# 04-AT86RF215IQ.net
KiCad netlist of a schematic drawn in Altium Designer
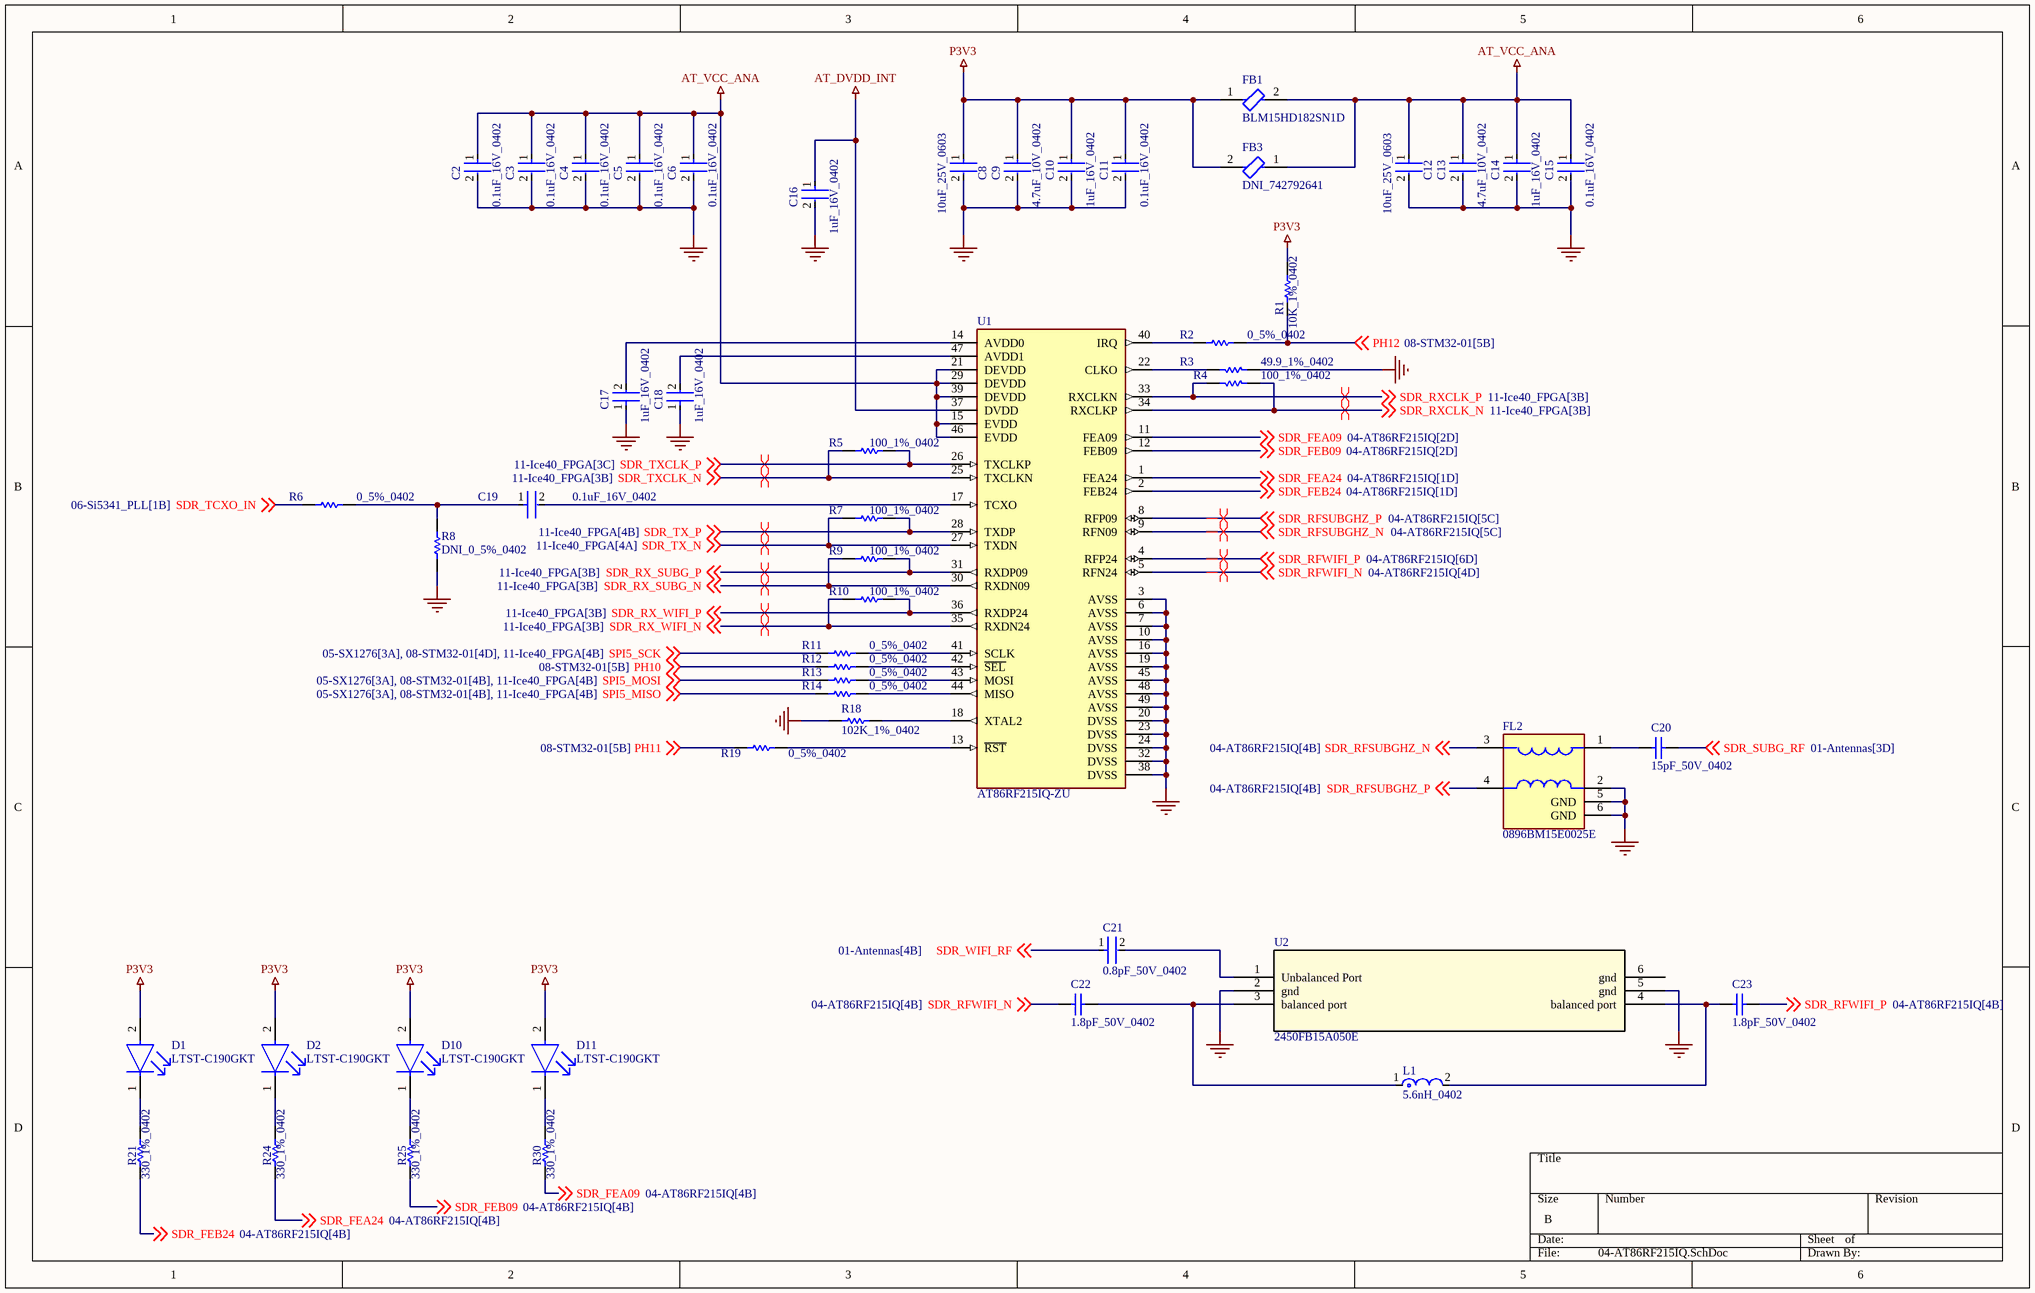
[diagram p0: 04-AT86RF215IQ.SchDoc]

(export (version "E")
  (design (tool "Eeschema 10.0.6"))
  (components
    (comp (ref "C2")
      (value "0.1uF_16V_0402")
      (footprint "FP-C0402-BB-MFG")
      (description "CAP CER 0.1UF 16V 5% X7R 0402")
      (fields
        (field (name "MANUFACTURER") "Kemet")
        (field (name "MANUFACTURER PART NUMBER") "C0402C104J4RACTU")
      )
      (libsource (lib "Altium Content Vault") (part "b4654b650e69147ec39a6b967a45e02"))
    )
    (comp (ref "C3")
      (value "0.1uF_16V_0402")
      (footprint "FP-C0402-BB-MFG")
      (description "CAP CER 0.1UF 16V 5% X7R 0402")
      (fields
        (field (name "MANUFACTURER") "Kemet")
        (field (name "MANUFACTURER PART NUMBER") "C0402C104J4RACTU")
      )
      (libsource (lib "Altium Content Vault") (part "b4654b650e69147ec39a6b967a45e02"))
    )
    (comp (ref "C4")
      (value "0.1uF_16V_0402")
      (footprint "FP-C0402-BB-MFG")
      (description "CAP CER 0.1UF 16V 5% X7R 0402")
      (fields
        (field (name "MANUFACTURER") "Kemet")
        (field (name "MANUFACTURER PART NUMBER") "C0402C104J4RACTU")
      )
      (libsource (lib "Altium Content Vault") (part "b4654b650e69147ec39a6b967a45e02"))
    )
    (comp (ref "C5")
      (value "0.1uF_16V_0402")
      (footprint "FP-C0402-BB-MFG")
      (description "CAP CER 0.1UF 16V 5% X7R 0402")
      (fields
        (field (name "MANUFACTURER") "Kemet")
        (field (name "MANUFACTURER PART NUMBER") "C0402C104J4RACTU")
      )
      (libsource (lib "Altium Content Vault") (part "b4654b650e69147ec39a6b967a45e02"))
    )
    (comp (ref "C6")
      (value "0.1uF_16V_0402")
      (footprint "FP-C0402-BB-MFG")
      (description "CAP CER 0.1UF 16V 5% X7R 0402")
      (fields
        (field (name "MANUFACTURER") "Kemet")
        (field (name "MANUFACTURER PART NUMBER") "C0402C104J4RACTU")
      )
      (libsource (lib "Altium Content Vault") (part "b4654b650e69147ec39a6b967a45e02"))
    )
    (comp (ref "C8")
      (value "10uF_25V_0603")
      (footprint "FP-CL10-IPC_C")
      (description "Cap Ceramic 10uF 25V X5R ±20% Pad SMD 0603 +85°C T/R")
      (fields (field (name "TOLERANCE") "20%"))
      (libsource (lib "Altium Content Vault") (part "b4654b650e69147ec39a6b967a45e02"))
    )
    (comp (ref "C9")
      (value "4.7uF_10V_0402")
      (footprint "FP-C1005-050-0_15-MFG")
      (description "CAP CER 4.7UF 10V X5R 0402")
      (fields (field (name "TOLERANCE") "10%"))
      (libsource (lib "Altium Content Vault") (part "b4654b650e69147ec39a6b967a45e02"))
    )
    (comp (ref "C10")
      (value "1uF_16V_0402")
      (footprint "FP-0402-L_1_0_0_05-W_0_5-IPC_A")
      (description "None")
      (fields (field (name "TOLERANCE") "10%"))
      (libsource (lib "Altium Content Vault") (part "b4654b650e69147ec39a6b967a45e02"))
    )
    (comp (ref "C11")
      (value "0.1uF_16V_0402")
      (footprint "FP-C0402-BB-MFG")
      (description "CAP CER 0.1UF 16V 5% X7R 0402")
      (fields
        (field (name "MANUFACTURER") "Kemet")
        (field (name "MANUFACTURER PART NUMBER") "C0402C104J4RACTU")
      )
      (libsource (lib "Altium Content Vault") (part "b4654b650e69147ec39a6b967a45e02"))
    )
    (comp (ref "C12")
      (value "10uF_25V_0603")
      (footprint "FP-CL10-IPC_C")
      (description "Cap Ceramic 10uF 25V X5R ±20% Pad SMD 0603 +85°C T/R")
      (fields (field (name "TOLERANCE") "20%"))
      (libsource (lib "Altium Content Vault") (part "b4654b650e69147ec39a6b967a45e02"))
    )
    (comp (ref "C13")
      (value "4.7uF_10V_0402")
      (footprint "FP-C1005-050-0_15-MFG")
      (description "CAP CER 4.7UF 10V X5R 0402")
      (fields (field (name "TOLERANCE") "10%"))
      (libsource (lib "Altium Content Vault") (part "b4654b650e69147ec39a6b967a45e02"))
    )
    (comp (ref "C14")
      (value "1uF_16V_0402")
      (footprint "FP-0402-L_1_0_0_05-W_0_5-IPC_A")
      (description "None")
      (fields (field (name "TOLERANCE") "10%"))
      (libsource (lib "Altium Content Vault") (part "b4654b650e69147ec39a6b967a45e02"))
    )
    (comp (ref "C15")
      (value "0.1uF_16V_0402")
      (footprint "FP-C0402-BB-MFG")
      (description "CAP CER 0.1UF 16V 5% X7R 0402")
      (fields
        (field (name "MANUFACTURER") "Kemet")
        (field (name "MANUFACTURER PART NUMBER") "C0402C104J4RACTU")
      )
      (libsource (lib "Altium Content Vault") (part "b4654b650e69147ec39a6b967a45e02"))
    )
    (comp (ref "C16")
      (value "1uF_16V_0402")
      (footprint "FP-0402-L_1_0_0_05-W_0_5-IPC_A")
      (description "None")
      (fields (field (name "TOLERANCE") "10%"))
      (libsource (lib "Altium Content Vault") (part "b4654b650e69147ec39a6b967a45e02"))
    )
    (comp (ref "C17")
      (value "1uF_16V_0402")
      (footprint "FP-0402-L_1_0_0_05-W_0_5-IPC_A")
      (description "None")
      (fields (field (name "TOLERANCE") "10%"))
      (libsource (lib "Altium Content Vault") (part "b4654b650e69147ec39a6b967a45e02"))
    )
    (comp (ref "C18")
      (value "1uF_16V_0402")
      (footprint "FP-0402-L_1_0_0_05-W_0_5-IPC_A")
      (description "None")
      (fields (field (name "TOLERANCE") "10%"))
      (libsource (lib "Altium Content Vault") (part "b4654b650e69147ec39a6b967a45e02"))
    )
    (comp (ref "C19")
      (value "0.1uF_16V_0402")
      (footprint "FP-C0402-BB-MFG")
      (description "CAP CER 0.1UF 16V 5% X7R 0402")
      (fields
        (field (name "MANUFACTURER") "Kemet")
        (field (name "MANUFACTURER PART NUMBER") "C0402C104J4RACTU")
      )
      (libsource (lib "Altium Content Vault") (part "b4654b650e69147ec39a6b967a45e02"))
    )
    (comp (ref "C20")
      (value "15pF_50V_0402")
      (footprint "CAPC1608X90X35ML10T15")
      (fields (field (name "PART NUMBER") "GRM1885C1H150JA01D") (field (name "MANUFACTURER") "Murata"))
      (libsource (lib "Altium Content Vault") (part "CAP"))
    )
    (comp (ref "C21")
      (value "0.8pF_50V_0402")
      (footprint "FP-GJM155-0_05-IPC_A")
      (description "Multi-Layer Ceramic Capacitor 0.8pF C0G  ±0.1pF 0402 Paper T/R")
      (fields (field (name "VOLTAGE") "50V"))
      (libsource (lib "Altium Content Vault") (part "02cd4be3c70576c341d710602a673aa"))
    )
    (comp (ref "C22")
      (value "1.8pF_50V_0402")
      (footprint "CAPC1005X55X25LL05T10")
      (fields (field (name "PART NUMBER") "GRM1555C1H1R8CA01D") (field (name "MANUFACTURER") "Murata"))
      (libsource (lib "Altium Content Vault") (part "CAP"))
    )
    (comp (ref "C23")
      (value "1.8pF_50V_0402")
      (footprint "CAPC1005X55X25LL05T10")
      (fields (field (name "PART NUMBER") "GRM1555C1H1R8CA01D") (field (name "MANUFACTURER") "Murata"))
      (libsource (lib "Altium Content Vault") (part "CAP"))
    )
    (comp (ref "D1")
      (value "LTST-C190GKT")
      (footprint "FP-LTST-C190GKT-MFG")
      (description "LED GREEN CLEAR CHIP SMD")
      (fields (field (name "VOLTAGE") "2V"))
      (libsource (lib "Altium Content Vault") (part "8706943c75ba83719d021d2fdc84c58"))
    )
    (comp (ref "D2")
      (value "LTST-C190GKT")
      (footprint "FP-LTST-C190GKT-MFG")
      (description "LED GREEN CLEAR CHIP SMD")
      (fields (field (name "VOLTAGE") "2V"))
      (libsource (lib "Altium Content Vault") (part "8706943c75ba83719d021d2fdc84c58"))
    )
    (comp (ref "D10")
      (value "LTST-C190GKT")
      (footprint "FP-LTST-C190GKT-MFG")
      (description "LED GREEN CLEAR CHIP SMD")
      (fields (field (name "VOLTAGE") "2V"))
      (libsource (lib "Altium Content Vault") (part "8706943c75ba83719d021d2fdc84c58"))
    )
    (comp (ref "D11")
      (value "LTST-C190GKT")
      (footprint "FP-LTST-C190GKT-MFG")
      (description "LED GREEN CLEAR CHIP SMD")
      (fields (field (name "VOLTAGE") "2V"))
      (libsource (lib "Altium Content Vault") (part "8706943c75ba83719d021d2fdc84c58"))
    )
    (comp (ref "FB1")
      (value "BLM15HD182SN1D")
      (footprint "FP-BLM15-0_05-MFG")
      (description "Chip Ferrite Bead, 0402, 1800Ω @ 100MHz, 2.2Ω, 25%, 200mA")
      (fields (field (name "TOLERANCE") "25%"))
      (libsource (lib "Altium Content Vault") (part "5f30dd21d616792df468990f7003faa"))
    )
    (comp (ref "FB3")
      (value "DNI_742792641")
      (footprint "FP-742792641-MFG")
      (description "FERRITE BEAD 300 OHM 0603 1LN")
      (fields (field (name "TOLERANCE") "25%"))
      (libsource (lib "Altium Content Vault") (part "5f30dd21d616792df468990f7003faa"))
    )
    (comp (ref "FL2")
      (value "0896BM15E0025E")
      (footprint "FP-0896BM15E0025E-MFG")
      (description "BALUN 863MHZ-928MHZ 50/50 0805")
      (fields
        (field (name "MANUFACTURER") "Johanson")
        (field (name "OCTOPART") "https://octopart.com/0896bm15e0025e-johanson-71691697")
      )
      (libsource (lib "Altium Content Vault") (part "9725e6fc3b6d4b71249fb6cd7b91a1d"))
    )
    (comp (ref "L1")
      (value "5.6nH_0402")
      (footprint "FP-LQG15HH_02-IPC_A")
      (description "Multilayer type RF Inductor 5.6nH ±0.3nH 0.18Ω 600mA 0402")
      (libsource (lib "Altium Content Vault") (part "4cc4b267dca4c8e51f7102f422741d8"))
    )
    (comp (ref "R1")
      (value "10K_1%_0402")
      (footprint "RESC1005X40X25NL10T10")
      (fields (field (name "MANUFACTURER") "Bourns") (field (name "PART NUMBER") "CR0402-FX-1002GLF"))
      (libsource (lib "Altium Content Vault") (part "RES"))
    )
    (comp (ref "R2")
      (value "0_5%_0402")
      (footprint "RESC1005X40X25NL05T10")
      (fields (field (name "MANUFACTURER") "Panasonic") (field (name "PART NUMBER") "ERJ-U020R00X"))
      (libsource (lib "Altium Content Vault") (part "RES"))
    )
    (comp (ref "R3")
      (value "49.9_1%_0402")
      (footprint "RESC1005X40X25NL10T10")
      (fields (field (name "PART NUMBER") "RK73H1ETTP49R9F") (field (name "MANUFACTURER") "KOA Speer"))
      (libsource (lib "Altium Content Vault") (part "RES"))
    )
    (comp (ref "R4")
      (value "100_1%_0402")
      (footprint "RESC1005X40X25NL05T10")
      (fields (field (name "MANUFACTURER") "Yageo") (field (name "PART NUMBER") "RC0402FR-13100RL"))
      (libsource (lib "Altium Content Vault") (part "RES"))
    )
    (comp (ref "R5")
      (value "100_1%_0402")
      (footprint "RESC1005X40X25NL05T10")
      (fields (field (name "MANUFACTURER") "Yageo") (field (name "PART NUMBER") "RC0402FR-13100RL"))
      (libsource (lib "Altium Content Vault") (part "RES"))
    )
    (comp (ref "R6")
      (value "0_5%_0402")
      (footprint "RESC1005X40X25NL05T10")
      (fields (field (name "MANUFACTURER") "Panasonic") (field (name "PART NUMBER") "ERJ-U020R00X"))
      (libsource (lib "Altium Content Vault") (part "RES"))
    )
    (comp (ref "R7")
      (value "100_1%_0402")
      (footprint "RESC1005X40X25NL05T10")
      (fields (field (name "MANUFACTURER") "Yageo") (field (name "PART NUMBER") "RC0402FR-13100RL"))
      (libsource (lib "Altium Content Vault") (part "RES"))
    )
    (comp (ref "R8")
      (value "DNI_0_5%_0402")
      (footprint "RESC1005X40X25NL05T10")
      (fields (field (name "MANUFACTURER") "Panasonic") (field (name "PART NUMBER") "ERJ-U020R00X"))
      (libsource (lib "Altium Content Vault") (part "RES"))
    )
    (comp (ref "R9")
      (value "100_1%_0402")
      (footprint "RESC1005X40X25NL05T10")
      (fields (field (name "MANUFACTURER") "Yageo") (field (name "PART NUMBER") "RC0402FR-13100RL"))
      (libsource (lib "Altium Content Vault") (part "RES"))
    )
    (comp (ref "R10")
      (value "100_1%_0402")
      (footprint "RESC1005X40X25NL05T10")
      (fields (field (name "MANUFACTURER") "Yageo") (field (name "PART NUMBER") "RC0402FR-13100RL"))
      (libsource (lib "Altium Content Vault") (part "RES"))
    )
    (comp (ref "R11")
      (value "0_5%_0402")
      (footprint "RESC1005X40X25NL05T10")
      (fields (field (name "MANUFACTURER") "Panasonic") (field (name "PART NUMBER") "ERJ-U020R00X"))
      (libsource (lib "Altium Content Vault") (part "RES"))
    )
    (comp (ref "R12")
      (value "0_5%_0402")
      (footprint "RESC1005X40X25NL05T10")
      (fields (field (name "MANUFACTURER") "Panasonic") (field (name "PART NUMBER") "ERJ-U020R00X"))
      (libsource (lib "Altium Content Vault") (part "RES"))
    )
    (comp (ref "R13")
      (value "0_5%_0402")
      (footprint "RESC1005X40X25NL05T10")
      (fields (field (name "MANUFACTURER") "Panasonic") (field (name "PART NUMBER") "ERJ-U020R00X"))
      (libsource (lib "Altium Content Vault") (part "RES"))
    )
    (comp (ref "R14")
      (value "0_5%_0402")
      (footprint "RESC1005X40X25NL05T10")
      (fields (field (name "MANUFACTURER") "Panasonic") (field (name "PART NUMBER") "ERJ-U020R00X"))
      (libsource (lib "Altium Content Vault") (part "RES"))
    )
    (comp (ref "R18")
      (value "102K_1%_0402")
      (footprint "RESC1005X40X25ML05T10")
      (fields (field (name "MANUFACTURER") "Yageo") (field (name "PART NUMBER") "RC0402FR-07102KL"))
      (libsource (lib "Altium Content Vault") (part "RES"))
    )
    (comp (ref "R19")
      (value "0_5%_0402")
      (footprint "RESC1005X40X25NL05T10")
      (fields (field (name "MANUFACTURER") "Panasonic") (field (name "PART NUMBER") "ERJ-U020R00X"))
      (libsource (lib "Altium Content Vault") (part "RES"))
    )
    (comp (ref "R21")
      (value "330_1%_0402")
      (footprint "RESC1005X40X25NL10T10")
      (fields (field (name "MANUFACTURER") "Panasonic") (field (name "PART NUMBER") "ERA-2AED331X"))
      (libsource (lib "Altium Content Vault") (part "RES"))
    )
    (comp (ref "R24")
      (value "330_1%_0402")
      (footprint "RESC1005X40X25NL10T10")
      (fields (field (name "MANUFACTURER") "Panasonic") (field (name "PART NUMBER") "ERA-2AED331X"))
      (libsource (lib "Altium Content Vault") (part "RES"))
    )
    (comp (ref "R25")
      (value "330_1%_0402")
      (footprint "RESC1005X40X25NL10T10")
      (fields (field (name "MANUFACTURER") "Panasonic") (field (name "PART NUMBER") "ERA-2AED331X"))
      (libsource (lib "Altium Content Vault") (part "RES"))
    )
    (comp (ref "R30")
      (value "330_1%_0402")
      (footprint "RESC1005X40X25NL10T10")
      (fields (field (name "MANUFACTURER") "Panasonic") (field (name "PART NUMBER") "ERA-2AED331X"))
      (libsource (lib "Altium Content Vault") (part "RES"))
    )
    (comp (ref "U1")
      (value "AT86RF215IQ-ZU")
      (footprint "FP-AT86RF215IQ-ZU-MFG")
      (description "IC RF TXRX 802.15.4 48VFQFN")
      (fields
        (field (name "MANUFACTURER") "Microchip")
        (field (name "OCTOPART") "https://octopart.com/at86rf215iq-zu-microchip-77758620")
      )
      (libsource (lib "Altium Content Vault") (part "c531c0ad6565c2a43c7312791734b45"))
    )
    (comp (ref "U2")
      (value "2450FB15A050E")
      (footprint "2450FB15A050E_JOT")
      (description "No Description Available")
      (libsource (lib "2450FB15A050E") (part "2450FB15A050E"))
    )
  )
  (nets
    (net (code "1") (name "AT_DVDD_INT") (class "Default")
      (node (ref "C16") (pin "1") (pinfunction "1_1") (pintype "passive"))
      (node (ref "U1") (pin "37") (pinfunction "DVDD_37") (pintype "power_in"))
    )
    (net (code "2") (name "AT_VCC_ANA") (class "Default")
      (node (ref "C12") (pin "1") (pinfunction "1_1") (pintype "passive"))
      (node (ref "C13") (pin "1") (pinfunction "1_1") (pintype "passive"))
      (node (ref "C14") (pin "1") (pinfunction "1_1") (pintype "passive"))
      (node (ref "C15") (pin "1") (pinfunction "1_1") (pintype "passive"))
      (node (ref "C2") (pin "1") (pinfunction "1_1") (pintype "passive"))
      (node (ref "C3") (pin "1") (pinfunction "1_1") (pintype "passive"))
      (node (ref "C4") (pin "1") (pinfunction "1_1") (pintype "passive"))
      (node (ref "C5") (pin "1") (pinfunction "1_1") (pintype "passive"))
      (node (ref "C6") (pin "1") (pinfunction "1_1") (pintype "passive"))
      (node (ref "FB1") (pin "2") (pinfunction "2_2") (pintype "passive"))
      (node (ref "FB3") (pin "1") (pinfunction "1_1") (pintype "passive"))
      (node (ref "U1") (pin "15") (pinfunction "EVDD_15") (pintype "power_in"))
      (node (ref "U1") (pin "21") (pinfunction "DEVDD_21") (pintype "power_in"))
      (node (ref "U1") (pin "29") (pinfunction "DEVDD_29") (pintype "power_in"))
      (node (ref "U1") (pin "39") (pinfunction "DEVDD_39") (pintype "power_in"))
      (node (ref "U1") (pin "46") (pinfunction "EVDD_46") (pintype "power_in"))
    )
    (net (code "3") (name "GND") (class "Default")
      (node (ref "C10") (pin "2") (pinfunction "2_2") (pintype "passive"))
      (node (ref "C11") (pin "2") (pinfunction "2_2") (pintype "passive"))
      (node (ref "C12") (pin "2") (pinfunction "2_2") (pintype "passive"))
      (node (ref "C13") (pin "2") (pinfunction "2_2") (pintype "passive"))
      (node (ref "C14") (pin "2") (pinfunction "2_2") (pintype "passive"))
      (node (ref "C15") (pin "2") (pinfunction "2_2") (pintype "passive"))
      (node (ref "C16") (pin "2") (pinfunction "2_2") (pintype "passive"))
      (node (ref "C17") (pin "1") (pinfunction "1_1") (pintype "passive"))
      (node (ref "C18") (pin "1") (pinfunction "1_1") (pintype "passive"))
      (node (ref "C2") (pin "2") (pinfunction "2_2") (pintype "passive"))
      (node (ref "C3") (pin "2") (pinfunction "2_2") (pintype "passive"))
      (node (ref "C4") (pin "2") (pinfunction "2_2") (pintype "passive"))
      (node (ref "C5") (pin "2") (pinfunction "2_2") (pintype "passive"))
      (node (ref "C6") (pin "2") (pinfunction "2_2") (pintype "passive"))
      (node (ref "C8") (pin "2") (pinfunction "2_2") (pintype "passive"))
      (node (ref "C9") (pin "2") (pinfunction "2_2") (pintype "passive"))
      (node (ref "FL2") (pin "2") (pinfunction "GND_2") (pintype "power_in"))
      (node (ref "FL2") (pin "5") (pinfunction "GND_5") (pintype "power_in"))
      (node (ref "FL2") (pin "6") (pinfunction "GND_6") (pintype "power_in"))
      (node (ref "R18") (pin "1") (pinfunction "1_1") (pintype "passive"))
      (node (ref "R3") (pin "2") (pinfunction "2_2") (pintype "passive"))
      (node (ref "R8") (pin "1") (pinfunction "1_1") (pintype "passive"))
      (node (ref "U1") (pin "10") (pinfunction "AVSS_10") (pintype "power_in"))
      (node (ref "U1") (pin "16") (pinfunction "AVSS_16") (pintype "power_in"))
      (node (ref "U1") (pin "19") (pinfunction "AVSS_19") (pintype "power_in"))
      (node (ref "U1") (pin "20") (pinfunction "DVSS_20") (pintype "power_in"))
      (node (ref "U1") (pin "23") (pinfunction "DVSS_23") (pintype "power_in"))
      (node (ref "U1") (pin "24") (pinfunction "DVSS_24") (pintype "power_in"))
      (node (ref "U1") (pin "3") (pinfunction "AVSS_3") (pintype "power_in"))
      (node (ref "U1") (pin "32") (pinfunction "DVSS_32") (pintype "power_in"))
      (node (ref "U1") (pin "38") (pinfunction "DVSS_38") (pintype "power_in"))
      (node (ref "U1") (pin "45") (pinfunction "AVSS_45") (pintype "power_in"))
      (node (ref "U1") (pin "48") (pinfunction "AVSS_48") (pintype "power_in"))
      (node (ref "U1") (pin "49") (pinfunction "AVSS_49") (pintype "power_in"))
      (node (ref "U1") (pin "6") (pinfunction "AVSS_6") (pintype "power_in"))
      (node (ref "U1") (pin "7") (pinfunction "AVSS_7") (pintype "power_in"))
      (node (ref "U2") (pin "2") (pinfunction "gnd_2") (pintype "passive"))
      (node (ref "U2") (pin "5") (pinfunction "gnd_5") (pintype "passive"))
    )
    (net (code "4") (name "Net-(C19-Pad1)") (class "Default")
      (node (ref "C19") (pin "1") (pinfunction "1_1") (pintype "passive"))
      (node (ref "R6") (pin "2") (pinfunction "2_2") (pintype "passive"))
      (node (ref "R8") (pin "2") (pinfunction "2_2") (pintype "passive"))
    )
    (net (code "5") (name "Net-(C22-Pad2)") (class "Default")
      (node (ref "C22") (pin "2") (pinfunction "2_2") (pintype "passive"))
      (node (ref "L1") (pin "1") (pinfunction "1_1") (pintype "passive"))
      (node (ref "U2") (pin "3") (pinfunction "balanced_port_3") (pintype "passive"))
    )
    (net (code "6") (name "Net-(C23-Pad1)") (class "Default")
      (node (ref "C23") (pin "1") (pinfunction "1_1") (pintype "passive"))
      (node (ref "L1") (pin "2") (pinfunction "2_2") (pintype "passive"))
      (node (ref "U2") (pin "4") (pinfunction "balanced_port_4") (pintype "passive"))
    )
    (net (code "7") (name "Net-(D1-C)") (class "Default")
      (node (ref "D1") (pin "1") (pinfunction "C_1") (pintype "passive"))
      (node (ref "R21") (pin "2") (pinfunction "2_2") (pintype "passive"))
    )
    (net (code "8") (name "Net-(D2-C)") (class "Default")
      (node (ref "D2") (pin "1") (pinfunction "C_1") (pintype "passive"))
      (node (ref "R24") (pin "2") (pinfunction "2_2") (pintype "passive"))
    )
    (net (code "9") (name "Net-(D10-C)") (class "Default")
      (node (ref "D10") (pin "1") (pinfunction "C_1") (pintype "passive"))
      (node (ref "R25") (pin "2") (pinfunction "2_2") (pintype "passive"))
    )
    (net (code "10") (name "Net-(D11-C)") (class "Default")
      (node (ref "D11") (pin "1") (pinfunction "C_1") (pintype "passive"))
      (node (ref "R30") (pin "2") (pinfunction "2_2") (pintype "passive"))
    )
    (net (code "11") (name "Net-(FL2-Unbalanced_Port)") (class "Default")
      (node (ref "C20") (pin "1") (pinfunction "1_1") (pintype "passive"))
      (node (ref "FL2") (pin "1") (pinfunction "Unbalanced_Port_1") (pintype "passive"))
    )
    (net (code "12") (name "Net-(U1-AVDD0)") (class "Default")
      (node (ref "C17") (pin "2") (pinfunction "2_2") (pintype "passive"))
      (node (ref "U1") (pin "14") (pinfunction "AVDD0_14") (pintype "power_in"))
    )
    (net (code "13") (name "Net-(U1-AVDD1)") (class "Default")
      (node (ref "C18") (pin "2") (pinfunction "2_2") (pintype "passive"))
      (node (ref "U1") (pin "47") (pinfunction "AVDD1_47") (pintype "power_in"))
    )
    (net (code "14") (name "Net-(U1-CLKO)") (class "Default")
      (node (ref "R3") (pin "1") (pinfunction "1_1") (pintype "passive"))
      (node (ref "U1") (pin "22") (pinfunction "CLKO_22") (pintype "output"))
    )
    (net (code "15") (name "Net-(U1-IRQ)") (class "Default")
      (node (ref "R2") (pin "1") (pinfunction "1_1") (pintype "passive"))
      (node (ref "U1") (pin "40") (pinfunction "IRQ_40") (pintype "output"))
    )
    (net (code "16") (name "Net-(U1-MISO)") (class "Default")
      (node (ref "R14") (pin "2") (pinfunction "2_2") (pintype "passive"))
      (node (ref "U1") (pin "44") (pinfunction "MISO_44") (pintype "output"))
    )
    (net (code "17") (name "Net-(U1-MOSI)") (class "Default")
      (node (ref "R13") (pin "2") (pinfunction "2_2") (pintype "passive"))
      (node (ref "U1") (pin "43") (pinfunction "MOSI_43") (pintype "input"))
    )
    (net (code "18") (name "Net-(U1-SCLK)") (class "Default")
      (node (ref "R11") (pin "2") (pinfunction "2_2") (pintype "passive"))
      (node (ref "U1") (pin "41") (pinfunction "SCLK_41") (pintype "input"))
    )
    (net (code "19") (name "Net-(U1-TCXO)") (class "Default")
      (node (ref "C19") (pin "2") (pinfunction "2_2") (pintype "passive"))
      (node (ref "U1") (pin "17") (pinfunction "TCXO_17") (pintype "input"))
    )
    (net (code "20") (name "Net-(U1-XTAL2)") (class "Default")
      (node (ref "R18") (pin "2") (pinfunction "2_2") (pintype "passive"))
      (node (ref "U1") (pin "18") (pinfunction "XTAL2_18") (pintype "output"))
    )
    (net (code "21") (name "Net-(U1-~{RST})") (class "Default")
      (node (ref "R19") (pin "2") (pinfunction "2_2") (pintype "passive"))
      (node (ref "U1") (pin "13") (pinfunction "~{RST}_13") (pintype "input"))
    )
    (net (code "22") (name "Net-(U1-~{SEL})") (class "Default")
      (node (ref "R12") (pin "2") (pinfunction "2_2") (pintype "passive"))
      (node (ref "U1") (pin "42") (pinfunction "~{SEL}_42") (pintype "input"))
    )
    (net (code "23") (name "Net-(U2-Unbalanced_Port)") (class "Default")
      (node (ref "C21") (pin "2") (pinfunction "2_2") (pintype "passive"))
      (node (ref "U2") (pin "1") (pinfunction "Unbalanced_Port_1") (pintype "passive"))
    )
    (net (code "24") (name "P3V3") (class "Default")
      (node (ref "C10") (pin "1") (pinfunction "1_1") (pintype "passive"))
      (node (ref "C11") (pin "1") (pinfunction "1_1") (pintype "passive"))
      (node (ref "C8") (pin "1") (pinfunction "1_1") (pintype "passive"))
      (node (ref "C9") (pin "1") (pinfunction "1_1") (pintype "passive"))
      (node (ref "D1") (pin "2") (pinfunction "A_2") (pintype "passive"))
      (node (ref "D10") (pin "2") (pinfunction "A_2") (pintype "passive"))
      (node (ref "D11") (pin "2") (pinfunction "A_2") (pintype "passive"))
      (node (ref "D2") (pin "2") (pinfunction "A_2") (pintype "passive"))
      (node (ref "FB1") (pin "1") (pinfunction "1_1") (pintype "passive"))
      (node (ref "FB3") (pin "2") (pinfunction "2_2") (pintype "passive"))
      (node (ref "R1") (pin "2") (pinfunction "2_2") (pintype "passive"))
    )
    (net (code "25") (name "PH10") (class "Default")
      (node (ref "R12") (pin "1") (pinfunction "1_1") (pintype "passive"))
    )
    (net (code "26") (name "PH11") (class "Default")
      (node (ref "R19") (pin "1") (pinfunction "1_1") (pintype "passive"))
    )
    (net (code "27") (name "PH12") (class "Default")
      (node (ref "R1") (pin "1") (pinfunction "1_1") (pintype "passive"))
      (node (ref "R2") (pin "2") (pinfunction "2_2") (pintype "passive"))
    )
    (net (code "28") (name "SDR_FEA09") (class "Default")
      (node (ref "R30") (pin "1") (pinfunction "1_1") (pintype "passive"))
      (node (ref "U1") (pin "11") (pinfunction "FEA09_11") (pintype "output"))
    )
    (net (code "29") (name "SDR_FEA24") (class "Default")
      (node (ref "R24") (pin "1") (pinfunction "1_1") (pintype "passive"))
      (node (ref "U1") (pin "1") (pinfunction "FEA24_1") (pintype "output"))
    )
    (net (code "30") (name "SDR_FEB09") (class "Default")
      (node (ref "R25") (pin "1") (pinfunction "1_1") (pintype "passive"))
      (node (ref "U1") (pin "12") (pinfunction "FEB09_12") (pintype "output"))
    )
    (net (code "31") (name "SDR_FEB24") (class "Default")
      (node (ref "R21") (pin "1") (pinfunction "1_1") (pintype "passive"))
      (node (ref "U1") (pin "2") (pinfunction "FEB24_2") (pintype "output"))
    )
    (net (code "32") (name "SDR_RFSUBGHZ_N") (class "Default")
      (node (ref "FL2") (pin "3") (pinfunction "1_Balanced_Port_3") (pintype "passive"))
      (node (ref "U1") (pin "9") (pinfunction "RFN09_9") (pintype "bidirectional"))
    )
    (net (code "33") (name "SDR_RFSUBGHZ_P") (class "Default")
      (node (ref "FL2") (pin "4") (pinfunction "2_Balanced_Port_4") (pintype "passive"))
      (node (ref "U1") (pin "8") (pinfunction "RFP09_8") (pintype "bidirectional"))
    )
    (net (code "34") (name "SDR_RFWIFI_N") (class "Default")
      (node (ref "C22") (pin "1") (pinfunction "1_1") (pintype "passive"))
      (node (ref "U1") (pin "5") (pinfunction "RFN24_5") (pintype "bidirectional"))
    )
    (net (code "35") (name "SDR_RFWIFI_P") (class "Default")
      (node (ref "C23") (pin "2") (pinfunction "2_2") (pintype "passive"))
      (node (ref "U1") (pin "4") (pinfunction "RFP24_4") (pintype "bidirectional"))
    )
    (net (code "36") (name "SDR_RXCLK_N") (class "Default")
      (node (ref "R4") (pin "1") (pinfunction "1_1") (pintype "passive"))
      (node (ref "U1") (pin "34") (pinfunction "RXCLKP_34") (pintype "output"))
    )
    (net (code "37") (name "SDR_RXCLK_P") (class "Default")
      (node (ref "R4") (pin "2") (pinfunction "2_2") (pintype "passive"))
      (node (ref "U1") (pin "33") (pinfunction "RXCLKN_33") (pintype "output"))
    )
    (net (code "38") (name "SDR_RX_SUBG_N") (class "Default")
      (node (ref "R9") (pin "1") (pinfunction "1_1") (pintype "passive"))
      (node (ref "U1") (pin "30") (pinfunction "RXDN09_30") (pintype "output"))
    )
    (net (code "39") (name "SDR_RX_SUBG_P") (class "Default")
      (node (ref "R9") (pin "2") (pinfunction "2_2") (pintype "passive"))
      (node (ref "U1") (pin "31") (pinfunction "RXDP09_31") (pintype "output"))
    )
    (net (code "40") (name "SDR_RX_WIFI_N") (class "Default")
      (node (ref "R10") (pin "1") (pinfunction "1_1") (pintype "passive"))
      (node (ref "U1") (pin "35") (pinfunction "RXDN24_35") (pintype "output"))
    )
    (net (code "41") (name "SDR_RX_WIFI_P") (class "Default")
      (node (ref "R10") (pin "2") (pinfunction "2_2") (pintype "passive"))
      (node (ref "U1") (pin "36") (pinfunction "RXDP24_36") (pintype "output"))
    )
    (net (code "42") (name "SDR_SUBG_RF") (class "Default")
      (node (ref "C20") (pin "2") (pinfunction "2_2") (pintype "passive"))
    )
    (net (code "43") (name "SDR_TCXO_IN") (class "Default")
      (node (ref "R6") (pin "1") (pinfunction "1_1") (pintype "passive"))
    )
    (net (code "44") (name "SDR_TXCLK_N") (class "Default")
      (node (ref "R5") (pin "1") (pinfunction "1_1") (pintype "passive"))
      (node (ref "U1") (pin "25") (pinfunction "TXCLKN_25") (pintype "input"))
    )
    (net (code "45") (name "SDR_TXCLK_P") (class "Default")
      (node (ref "R5") (pin "2") (pinfunction "2_2") (pintype "passive"))
      (node (ref "U1") (pin "26") (pinfunction "TXCLKP_26") (pintype "input"))
    )
    (net (code "46") (name "SDR_TX_N") (class "Default")
      (node (ref "R7") (pin "1") (pinfunction "1_1") (pintype "passive"))
      (node (ref "U1") (pin "27") (pinfunction "TXDN_27") (pintype "input"))
    )
    (net (code "47") (name "SDR_TX_P") (class "Default")
      (node (ref "R7") (pin "2") (pinfunction "2_2") (pintype "passive"))
      (node (ref "U1") (pin "28") (pinfunction "TXDP_28") (pintype "input"))
    )
    (net (code "48") (name "SDR_WIFI_RF") (class "Default")
      (node (ref "C21") (pin "1") (pinfunction "1_1") (pintype "passive"))
    )
    (net (code "49") (name "SPI5_MISO") (class "Default")
      (node (ref "R14") (pin "1") (pinfunction "1_1") (pintype "passive"))
    )
    (net (code "50") (name "SPI5_MOSI") (class "Default")
      (node (ref "R13") (pin "1") (pinfunction "1_1") (pintype "passive"))
    )
    (net (code "51") (name "SPI5_SCK") (class "Default")
      (node (ref "R11") (pin "1") (pinfunction "1_1") (pintype "passive"))
    )
    (net (code "52") (name "unconnected-(U2-gnd-Pad6)") (class "Default")
      (node (ref "U2") (pin "6") (pinfunction "gnd_6") (pintype "passive"))
    )
  )
)
